# Panel.net
KiCad netlist of a schematic drawn in EAGLE
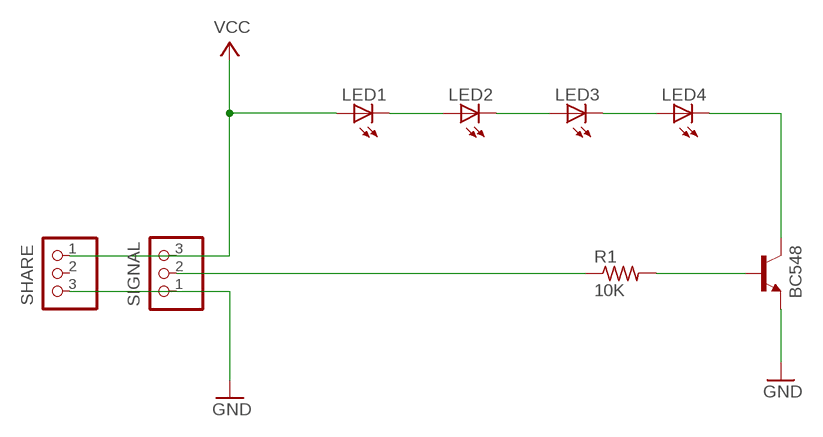
[diagram p0: schematic, sheet 1]

(export (version "E")
  (design (tool "Eeschema 10.0.6"))
  (components
    (comp (ref "LED1")
      (value "LED10MM")
      (footprint "eagle-import:LED10MM")
      (libsource (lib "eagle-import") (part "LED10MM"))
    )
    (comp (ref "LED2")
      (value "LED10MM")
      (footprint "eagle-import:LED10MM")
      (libsource (lib "eagle-import") (part "LED10MM"))
    )
    (comp (ref "LED3")
      (value "LED10MM")
      (footprint "eagle-import:LED10MM")
      (libsource (lib "eagle-import") (part "LED10MM"))
    )
    (comp (ref "LED4")
      (value "LED10MM")
      (footprint "eagle-import:LED10MM")
      (libsource (lib "eagle-import") (part "LED10MM"))
    )
    (comp (ref "Q1")
      (value "BC548")
      (footprint "eagle-import:TO92-EBC")
      (libsource (lib "eagle-import") (part "BC548"))
    )
    (comp (ref "R1")
      (value "10K")
      (footprint "eagle-import:0204_7")
      (libsource (lib "eagle-import") (part "R-US_0204/7"))
    )
    (comp (ref "SHARE")
      (value "PINHD-1X3/90")
      (footprint "eagle-import:1X03_90")
      (libsource (lib "eagle-import") (part "PINHD-1X3/90"))
    )
    (comp (ref "SIGNAL")
      (value "PINHD-1X3/90")
      (footprint "eagle-import:1X03_90")
      (libsource (lib "eagle-import") (part "PINHD-1X3/90"))
    )
  )
  (nets
    (net (code "1") (name "GND") (class "Default")
      (node (ref "Q1") (pin "E") (pinfunction "E_E") (pintype "passive"))
      (node (ref "SHARE") (pin "3") (pinfunction "3_3") (pintype "passive"))
      (node (ref "SIGNAL") (pin "1") (pinfunction "1_1") (pintype "passive"))
    )
    (net (code "2") (name "Net-(LED1-C)") (class "Default")
      (node (ref "LED1") (pin "K") (pinfunction "C_K") (pintype "passive"))
      (node (ref "LED2") (pin "A") (pinfunction "A_A") (pintype "passive"))
    )
    (net (code "3") (name "Net-(LED2-C)") (class "Default")
      (node (ref "LED2") (pin "K") (pinfunction "C_K") (pintype "passive"))
      (node (ref "LED3") (pin "A") (pinfunction "A_A") (pintype "passive"))
    )
    (net (code "4") (name "Net-(LED3-C)") (class "Default")
      (node (ref "LED3") (pin "K") (pinfunction "C_K") (pintype "passive"))
      (node (ref "LED4") (pin "A") (pinfunction "A_A") (pintype "passive"))
    )
    (net (code "5") (name "Net-(LED4-C)") (class "Default")
      (node (ref "LED4") (pin "K") (pinfunction "C_K") (pintype "passive"))
      (node (ref "Q1") (pin "C") (pinfunction "C_C") (pintype "passive"))
    )
    (net (code "6") (name "Net-(Q1-PadB)") (class "Default")
      (node (ref "Q1") (pin "B") (pinfunction "B_B") (pintype "passive"))
      (node (ref "R1") (pin "2") (pinfunction "2_2") (pintype "passive"))
    )
    (net (code "7") (name "Net-(R1-Pad1)") (class "Default")
      (node (ref "R1") (pin "1") (pinfunction "1_1") (pintype "passive"))
      (node (ref "SIGNAL") (pin "2") (pinfunction "2_2") (pintype "passive"))
    )
    (net (code "8") (name "VCC") (class "Default")
      (node (ref "LED1") (pin "A") (pinfunction "A_A") (pintype "passive"))
      (node (ref "SHARE") (pin "1") (pinfunction "1_1") (pintype "passive"))
      (node (ref "SIGNAL") (pin "3") (pinfunction "3_3") (pintype "passive"))
    )
    (net (code "9") (name "unconnected-(SHARE-Pad2)") (class "Default")
      (node (ref "SHARE") (pin "2") (pinfunction "2_2") (pintype "passive"))
    )
  )
)
